# SCH_WiFiBTBitbanging_2025-02-11.net
KiCad netlist of a schematic drawn in EasyEDA
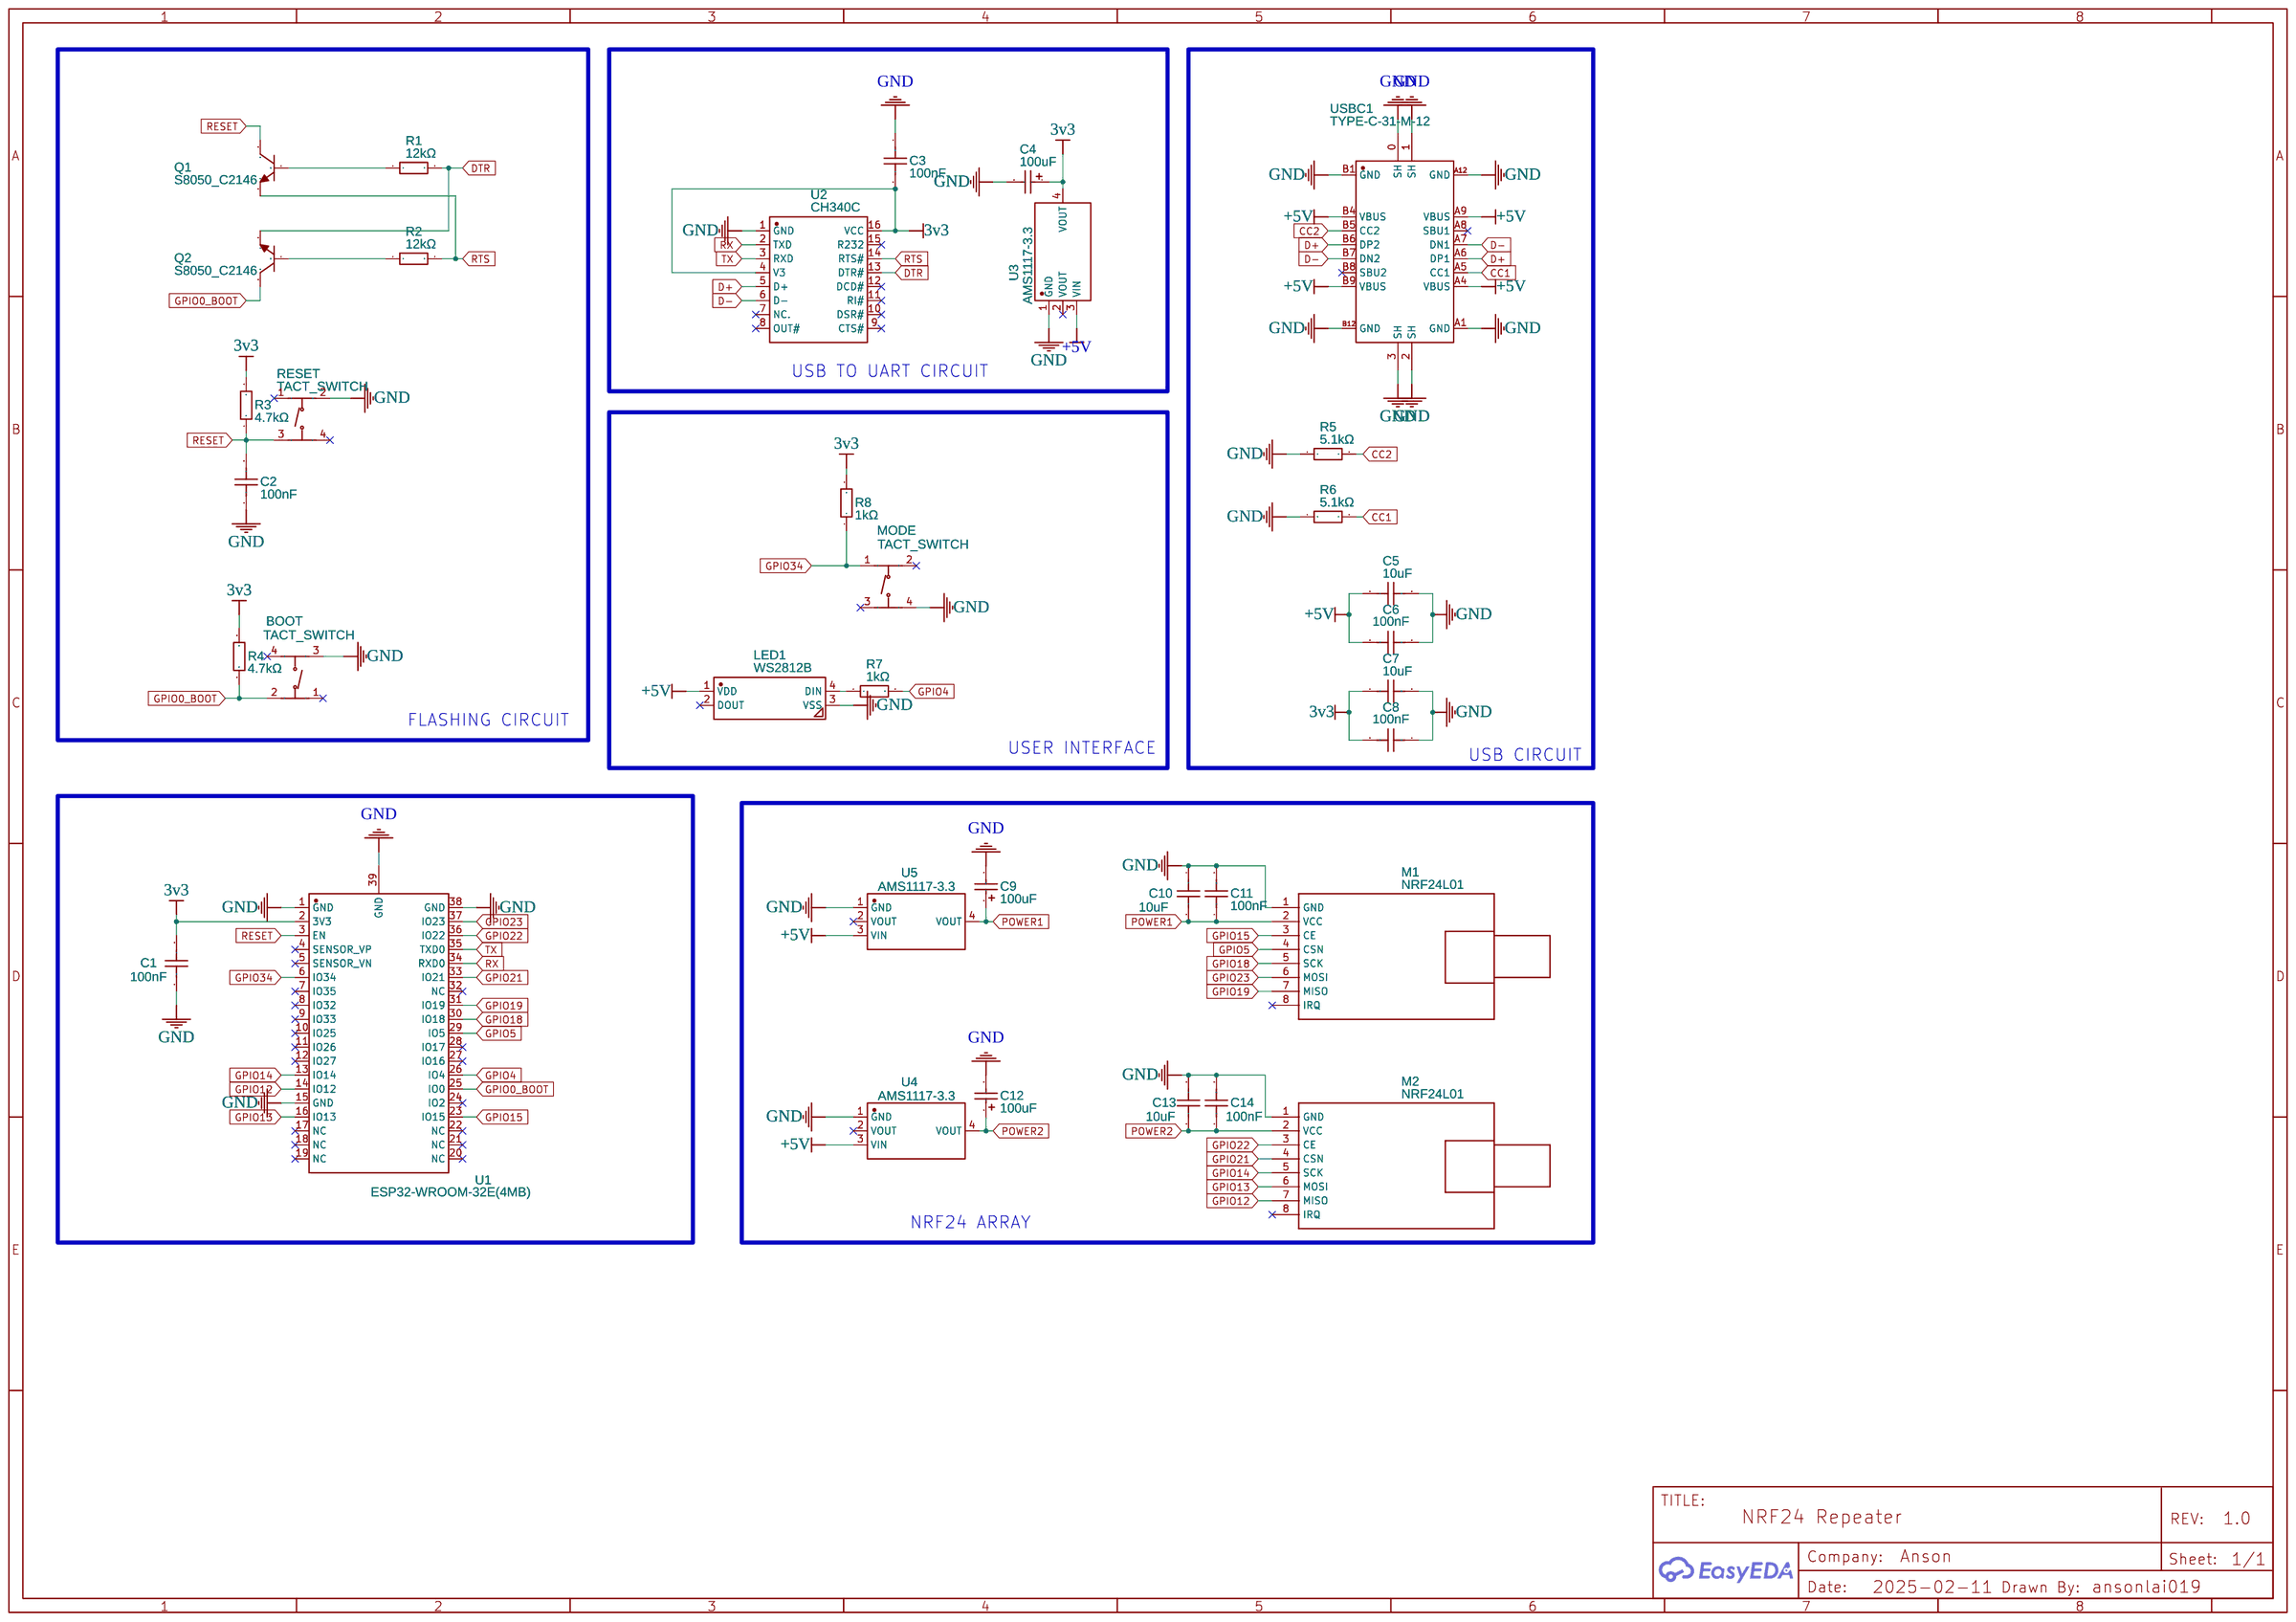
[diagram p0: schematic sheet]

(export (version "E")
  (design (tool "Eeschema 10.0.6"))
  (components
    (comp (ref "BOOT")
      (value "TACT_SWITCH")
      (fields
        (field (name "Manufacturer Part") "TS-1187A-B-A-B")
        (field (name "Manufacturer") "XKB Connectivity(中国星坤)")
      )
      (libsource (lib "") (part "TS-1187A-B-A-B"))
    )
    (comp (ref "C1")
      (value "100nF")
      (fields
        (field (name "Manufacturer Part") "CC0805KRX7R9BB104")
        (field (name "Manufacturer") "YAGEO(国巨)")
      )
      (libsource (lib "") (part "CC0805KRX7R9BB104"))
    )
    (comp (ref "C2")
      (value "100nF")
      (fields
        (field (name "Manufacturer Part") "CC0805KRX7R9BB104")
        (field (name "Manufacturer") "YAGEO(国巨)")
      )
      (libsource (lib "") (part "CC0805KRX7R9BB104"))
    )
    (comp (ref "C3")
      (value "100nF")
      (fields
        (field (name "Manufacturer Part") "CC0805KRX7R9BB104")
        (field (name "Manufacturer") "YAGEO(国巨)")
      )
      (libsource (lib "") (part "CC0805KRX7R9BB104_2"))
    )
    (comp (ref "C4")
      (value "100uF")
      (fields (field (name "Manufacturer Part") "TAJB107K006RNJ") (field (name "Manufacturer") "Kyocera AVX"))
      (libsource (lib "") (part "TAJB107K006RNJ_1"))
    )
    (comp (ref "C5")
      (value "10uF")
      (fields
        (field (name "Manufacturer Part") "CL21A106KAYNNNE")
        (field (name "Manufacturer") "SAMSUNG(三星)")
      )
      (libsource (lib "") (part "CL21A106KAYNNNE"))
    )
    (comp (ref "C6")
      (value "100nF")
      (fields
        (field (name "Manufacturer Part") "CC0805KRX7R9BB104")
        (field (name "Manufacturer") "YAGEO(国巨)")
      )
      (libsource (lib "") (part "CC0805KRX7R9BB104_1"))
    )
    (comp (ref "C7")
      (value "10uF")
      (fields
        (field (name "Manufacturer Part") "CL21A106KAYNNNE")
        (field (name "Manufacturer") "SAMSUNG(三星)")
      )
      (libsource (lib "") (part "CL21A106KAYNNNE"))
    )
    (comp (ref "C8")
      (value "100nF")
      (fields
        (field (name "Manufacturer Part") "CC0805KRX7R9BB104")
        (field (name "Manufacturer") "YAGEO(国巨)")
      )
      (libsource (lib "") (part "CC0805KRX7R9BB104_1"))
    )
    (comp (ref "C9")
      (value "100uF")
      (fields (field (name "Manufacturer Part") "TAJB107K006RNJ") (field (name "Manufacturer") "Kyocera AVX"))
      (libsource (lib "") (part "TAJB107K006RNJ"))
    )
    (comp (ref "C10")
      (value "10uF")
      (fields
        (field (name "Manufacturer Part") "CL21A106KAYNNNE")
        (field (name "Manufacturer") "SAMSUNG(三星)")
      )
      (libsource (lib "") (part "CL21A106KAYNNNE_1"))
    )
    (comp (ref "C11")
      (value "100nF")
      (fields
        (field (name "Manufacturer Part") "CC0805KRX7R9BB104")
        (field (name "Manufacturer") "YAGEO(国巨)")
      )
      (libsource (lib "") (part "CC0805KRX7R9BB104"))
    )
    (comp (ref "C12")
      (value "100uF")
      (fields (field (name "Manufacturer Part") "TAJB107K006RNJ") (field (name "Manufacturer") "Kyocera AVX"))
      (libsource (lib "") (part "TAJB107K006RNJ"))
    )
    (comp (ref "C13")
      (value "10uF")
      (fields
        (field (name "Manufacturer Part") "CL21A106KAYNNNE")
        (field (name "Manufacturer") "SAMSUNG(三星)")
      )
      (libsource (lib "") (part "CL21A106KAYNNNE_1"))
    )
    (comp (ref "C14")
      (value "100nF")
      (fields
        (field (name "Manufacturer Part") "CC0805KRX7R9BB104")
        (field (name "Manufacturer") "YAGEO(国巨)")
      )
      (libsource (lib "") (part "CC0805KRX7R9BB104"))
    )
    (comp (ref "LED1")
      (value "WS2812B")
      (fields (field (name "Manufacturer Part") "WS2812B-B/T") (field (name "Manufacturer") "worldsemi"))
      (libsource (lib "") (part "WS2812B-B/W"))
    )
    (comp (ref "M1") (value "NRF24L01") (libsource (lib "") (part "WIRELESS-NRF24L01-PA-EXT")))
    (comp (ref "M2") (value "NRF24L01") (libsource (lib "") (part "WIRELESS-NRF24L01-PA-EXT")))
    (comp (ref "MODE")
      (value "TACT_SWITCH")
      (fields
        (field (name "Manufacturer Part") "TS-1187A-B-A-B")
        (field (name "Manufacturer") "XKB Connectivity(中国星坤)")
      )
      (libsource (lib "") (part "TS-1187A-B-A-B_2"))
    )
    (comp (ref "Q1")
      (value "S8050_C2146")
      (fields
        (field (name "Manufacturer Part") "S8050 J3Y(RANGE:200-350)")
        (field (name "Manufacturer") "CJ(江苏长电/长晶)")
      )
      (libsource (lib "") (part "S8050_C2146_1"))
    )
    (comp (ref "Q2")
      (value "S8050_C2146")
      (fields
        (field (name "Manufacturer Part") "S8050 J3Y(RANGE:200-350)")
        (field (name "Manufacturer") "CJ(江苏长电/长晶)")
      )
      (libsource (lib "") (part "S8050_C2146"))
    )
    (comp (ref "R1")
      (value "12kΩ")
      (fields
        (field (name "Manufacturer Part") "0805W8F1202T5E")
        (field (name "Manufacturer") "UNI-ROYAL(厚声)")
      )
      (libsource (lib "") (part "0805W8F1202T5E"))
    )
    (comp (ref "R2")
      (value "12kΩ")
      (fields
        (field (name "Manufacturer Part") "0805W8F1202T5E")
        (field (name "Manufacturer") "UNI-ROYAL(厚声)")
      )
      (libsource (lib "") (part "0805W8F1202T5E"))
    )
    (comp (ref "R3")
      (value "4.7kΩ")
      (fields
        (field (name "Manufacturer Part") "0805W8F4701T5E")
        (field (name "Manufacturer") "UNI-ROYAL(厚声)")
      )
      (libsource (lib "") (part "0805W8F4701T5E"))
    )
    (comp (ref "R4")
      (value "4.7kΩ")
      (fields
        (field (name "Manufacturer Part") "0805W8F4701T5E")
        (field (name "Manufacturer") "UNI-ROYAL(厚声)")
      )
      (libsource (lib "") (part "0805W8F4701T5E"))
    )
    (comp (ref "R5")
      (value "5.1kΩ")
      (fields
        (field (name "Manufacturer Part") "0805W8F5101T5E")
        (field (name "Manufacturer") "UNI-ROYAL(厚声)")
      )
      (libsource (lib "") (part "0805W8F5101T5E"))
    )
    (comp (ref "R6")
      (value "5.1kΩ")
      (fields
        (field (name "Manufacturer Part") "0805W8F5101T5E")
        (field (name "Manufacturer") "UNI-ROYAL(厚声)")
      )
      (libsource (lib "") (part "0805W8F5101T5E"))
    )
    (comp (ref "R7")
      (value "1kΩ")
      (fields
        (field (name "Manufacturer Part") "0805W8F1001T5E")
        (field (name "Manufacturer") "UNI-ROYAL(厚声)")
      )
      (libsource (lib "") (part "0805W8F1001T5E"))
    )
    (comp (ref "R8")
      (value "1kΩ")
      (fields
        (field (name "Manufacturer Part") "0805W8F1001T5E")
        (field (name "Manufacturer") "UNI-ROYAL(厚声)")
      )
      (libsource (lib "") (part "0805W8F1001T5E_1"))
    )
    (comp (ref "RESET")
      (value "TACT_SWITCH")
      (fields
        (field (name "Manufacturer Part") "TS-1187A-B-A-B")
        (field (name "Manufacturer") "XKB Connectivity(中国星坤)")
      )
      (libsource (lib "") (part "TS-1187A-B-A-B_1"))
    )
    (comp (ref "U1")
      (value "ESP32-WROOM-32E(4MB)")
      (fields
        (field (name "Manufacturer Part") "ESP32-WROOM-32E-N4")
        (field (name "Manufacturer") "ESPRESSIF(乐鑫)")
      )
      (libsource (lib "") (part "ESP32-WROOM-32E(4MB)"))
    )
    (comp (ref "U2")
      (value "CH340C")
      (fields (field (name "Manufacturer") "WCH(南京沁恒)"))
      (libsource (lib "") (part "CH340C"))
    )
    (comp (ref "U3")
      (value "AMS1117-3.3")
      (fields (field (name "Manufacturer") "AMS"))
      (libsource (lib "") (part "AMS1117-3.3"))
    )
    (comp (ref "U4")
      (value "AMS1117-3.3")
      (fields (field (name "Manufacturer") "AMS"))
      (libsource (lib "") (part "AMS1117-3.3_1"))
    )
    (comp (ref "U5")
      (value "AMS1117-3.3")
      (fields (field (name "Manufacturer") "AMS"))
      (libsource (lib "") (part "AMS1117-3.3_1"))
    )
    (comp (ref "USBC1")
      (value "TYPE-C-31-M-12")
      (fields (field (name "Manufacturer") "韩国韩荣"))
      (libsource (lib "") (part "TYPE-C-31-M-12"))
    )
  )
  (nets
    (net (code "1") (name "+5V") (class "Default")
      (node (ref "C5") (pin "1") (pinfunction "1_1") (pintype "unspecified"))
      (node (ref "C6") (pin "2") (pinfunction "2_2") (pintype "unspecified"))
      (node (ref "LED1") (pin "1") (pinfunction "VDD_1") (pintype "unspecified"))
      (node (ref "U3") (pin "3") (pinfunction "VIN_3") (pintype "unspecified"))
      (node (ref "U4") (pin "3") (pinfunction "VIN_3") (pintype "unspecified"))
      (node (ref "U5") (pin "3") (pinfunction "VIN_3") (pintype "unspecified"))
      (node (ref "USBC1") (pin "A4") (pinfunction "VBUS_A4") (pintype "unspecified"))
      (node (ref "USBC1") (pin "A9") (pinfunction "VBUS_A9") (pintype "unspecified"))
      (node (ref "USBC1") (pin "B4") (pinfunction "VBUS_B4") (pintype "unspecified"))
      (node (ref "USBC1") (pin "B9") (pinfunction "VBUS_B9") (pintype "unspecified"))
    )
    (net (code "2") (name "3v3") (class "Default")
      (node (ref "C1") (pin "2") (pinfunction "2_2") (pintype "unspecified"))
      (node (ref "C3") (pin "2") (pinfunction "2_2") (pintype "unspecified"))
      (node (ref "C4") (pin "1") (pinfunction "1_1") (pintype "input"))
      (node (ref "C7") (pin "1") (pinfunction "1_1") (pintype "unspecified"))
      (node (ref "C8") (pin "2") (pinfunction "2_2") (pintype "unspecified"))
      (node (ref "R3") (pin "2") (pinfunction "2_2") (pintype "input"))
      (node (ref "R4") (pin "2") (pinfunction "2_2") (pintype "input"))
      (node (ref "R8") (pin "2") (pinfunction "2_2") (pintype "input"))
      (node (ref "U1") (pin "2") (pinfunction "3V3_2") (pintype "unspecified"))
      (node (ref "U2") (pin "16") (pinfunction "VCC_16") (pintype "unspecified"))
      (node (ref "U2") (pin "4") (pinfunction "V3_4") (pintype "unspecified"))
      (node (ref "U3") (pin "4") (pinfunction "VOUT_4") (pintype "unspecified"))
    )
    (net (code "3") (name "CC1") (class "Default")
      (node (ref "R6") (pin "2") (pinfunction "2_2") (pintype "input"))
      (node (ref "USBC1") (pin "A5") (pinfunction "CC1_A5") (pintype "unspecified"))
    )
    (net (code "4") (name "CC2") (class "Default")
      (node (ref "R5") (pin "2") (pinfunction "2_2") (pintype "input"))
      (node (ref "USBC1") (pin "B5") (pinfunction "CC2_B5") (pintype "unspecified"))
    )
    (net (code "5") (name "D+") (class "Default")
      (node (ref "U2") (pin "5") (pinfunction "D+_5") (pintype "unspecified"))
      (node (ref "USBC1") (pin "A6") (pinfunction "DP1_A6") (pintype "unspecified"))
      (node (ref "USBC1") (pin "B6") (pinfunction "DP2_B6") (pintype "unspecified"))
    )
    (net (code "6") (name "D-") (class "Default")
      (node (ref "U2") (pin "6") (pinfunction "D-_6") (pintype "unspecified"))
      (node (ref "USBC1") (pin "A7") (pinfunction "DN1_A7") (pintype "unspecified"))
      (node (ref "USBC1") (pin "B7") (pinfunction "DN2_B7") (pintype "unspecified"))
    )
    (net (code "7") (name "DTR") (class "Default")
      (node (ref "Q2") (pin "2") (pinfunction "E_2") (pintype "unspecified"))
      (node (ref "R1") (pin "2") (pinfunction "2_2") (pintype "input"))
      (node (ref "U2") (pin "13") (pinfunction "DTR#_13") (pintype "unspecified"))
    )
    (net (code "8") (name "GND") (class "Default")
      (node (ref "BOOT") (pin "3") (pinfunction "C_3") (pintype "unspecified"))
      (node (ref "C1") (pin "1") (pinfunction "1_1") (pintype "unspecified"))
      (node (ref "C10") (pin "1") (pinfunction "1_1") (pintype "unspecified"))
      (node (ref "C11") (pin "2") (pinfunction "2_2") (pintype "unspecified"))
      (node (ref "C12") (pin "2") (pinfunction "2_2") (pintype "input"))
      (node (ref "C13") (pin "1") (pinfunction "1_1") (pintype "unspecified"))
      (node (ref "C14") (pin "2") (pinfunction "2_2") (pintype "unspecified"))
      (node (ref "C2") (pin "1") (pinfunction "1_1") (pintype "unspecified"))
      (node (ref "C3") (pin "1") (pinfunction "1_1") (pintype "unspecified"))
      (node (ref "C4") (pin "2") (pinfunction "2_2") (pintype "input"))
      (node (ref "C5") (pin "2") (pinfunction "2_2") (pintype "unspecified"))
      (node (ref "C6") (pin "1") (pinfunction "1_1") (pintype "unspecified"))
      (node (ref "C7") (pin "2") (pinfunction "2_2") (pintype "unspecified"))
      (node (ref "C8") (pin "1") (pinfunction "1_1") (pintype "unspecified"))
      (node (ref "C9") (pin "2") (pinfunction "2_2") (pintype "input"))
      (node (ref "LED1") (pin "3") (pinfunction "VSS_3") (pintype "unspecified"))
      (node (ref "M1") (pin "1") (pinfunction "GND_1") (pintype "bidirectional"))
      (node (ref "M2") (pin "1") (pinfunction "GND_1") (pintype "bidirectional"))
      (node (ref "MODE") (pin "4") (pinfunction "D_4") (pintype "unspecified"))
      (node (ref "R5") (pin "1") (pinfunction "1_1") (pintype "input"))
      (node (ref "R6") (pin "1") (pinfunction "1_1") (pintype "input"))
      (node (ref "RESET") (pin "2") (pinfunction "B_2") (pintype "unspecified"))
      (node (ref "U1") (pin "1") (pinfunction "GND_1") (pintype "unspecified"))
      (node (ref "U1") (pin "15") (pinfunction "GND_15") (pintype "unspecified"))
      (node (ref "U1") (pin "38") (pinfunction "GND_38") (pintype "unspecified"))
      (node (ref "U1") (pin "39") (pinfunction "GND_39") (pintype "unspecified"))
      (node (ref "U2") (pin "1") (pinfunction "GND_1") (pintype "unspecified"))
      (node (ref "U3") (pin "1") (pinfunction "GND_1") (pintype "unspecified"))
      (node (ref "U4") (pin "1") (pinfunction "GND_1") (pintype "unspecified"))
      (node (ref "U5") (pin "1") (pinfunction "GND_1") (pintype "unspecified"))
      (node (ref "USBC1") (pin "0") (pinfunction "SH_0") (pintype "unspecified"))
      (node (ref "USBC1") (pin "1") (pinfunction "SH_1") (pintype "unspecified"))
      (node (ref "USBC1") (pin "2") (pinfunction "SH_2") (pintype "unspecified"))
      (node (ref "USBC1") (pin "3") (pinfunction "SH_3") (pintype "unspecified"))
      (node (ref "USBC1") (pin "A1") (pinfunction "GND_A1") (pintype "unspecified"))
      (node (ref "USBC1") (pin "A12") (pinfunction "GND_A12") (pintype "unspecified"))
      (node (ref "USBC1") (pin "B1") (pinfunction "GND_B1") (pintype "unspecified"))
      (node (ref "USBC1") (pin "B12") (pinfunction "GND_B12") (pintype "unspecified"))
    )
    (net (code "9") (name "GPIO0_BOOT") (class "Default")
      (node (ref "BOOT") (pin "2") (pinfunction "B_2") (pintype "unspecified"))
      (node (ref "Q2") (pin "3") (pinfunction "C_3") (pintype "unspecified"))
      (node (ref "R4") (pin "1") (pinfunction "1_1") (pintype "input"))
      (node (ref "U1") (pin "25") (pinfunction "IO0_25") (pintype "unspecified"))
    )
    (net (code "10") (name "GPIO4") (class "Default")
      (node (ref "R7") (pin "2") (pinfunction "2_2") (pintype "input"))
      (node (ref "U1") (pin "26") (pinfunction "IO4_26") (pintype "unspecified"))
    )
    (net (code "11") (name "GPIO5") (class "Default")
      (node (ref "M1") (pin "4") (pinfunction "CSN_4") (pintype "bidirectional"))
      (node (ref "U1") (pin "29") (pinfunction "IO5_29") (pintype "unspecified"))
    )
    (net (code "12") (name "GPIO12") (class "Default")
      (node (ref "M2") (pin "7") (pinfunction "MISO_7") (pintype "bidirectional"))
      (node (ref "U1") (pin "14") (pinfunction "IO12_14") (pintype "unspecified"))
    )
    (net (code "13") (name "GPIO13") (class "Default")
      (node (ref "M2") (pin "6") (pinfunction "MOSI_6") (pintype "bidirectional"))
      (node (ref "U1") (pin "16") (pinfunction "IO13_16") (pintype "unspecified"))
    )
    (net (code "14") (name "GPIO14") (class "Default")
      (node (ref "M2") (pin "5") (pinfunction "SCK_5") (pintype "bidirectional"))
      (node (ref "U1") (pin "13") (pinfunction "IO14_13") (pintype "unspecified"))
    )
    (net (code "15") (name "GPIO15") (class "Default")
      (node (ref "M1") (pin "3") (pinfunction "CE_3") (pintype "bidirectional"))
      (node (ref "U1") (pin "23") (pinfunction "IO15_23") (pintype "unspecified"))
    )
    (net (code "16") (name "GPIO18") (class "Default")
      (node (ref "M1") (pin "5") (pinfunction "SCK_5") (pintype "bidirectional"))
      (node (ref "U1") (pin "30") (pinfunction "IO18_30") (pintype "unspecified"))
    )
    (net (code "17") (name "GPIO19") (class "Default")
      (node (ref "M1") (pin "7") (pinfunction "MISO_7") (pintype "bidirectional"))
      (node (ref "U1") (pin "31") (pinfunction "IO19_31") (pintype "unspecified"))
    )
    (net (code "18") (name "GPIO21") (class "Default")
      (node (ref "M2") (pin "4") (pinfunction "CSN_4") (pintype "bidirectional"))
      (node (ref "U1") (pin "33") (pinfunction "IO21_33") (pintype "unspecified"))
    )
    (net (code "19") (name "GPIO22") (class "Default")
      (node (ref "M2") (pin "3") (pinfunction "CE_3") (pintype "bidirectional"))
      (node (ref "U1") (pin "36") (pinfunction "IO22_36") (pintype "unspecified"))
    )
    (net (code "20") (name "GPIO23") (class "Default")
      (node (ref "M1") (pin "6") (pinfunction "MOSI_6") (pintype "bidirectional"))
      (node (ref "U1") (pin "37") (pinfunction "IO23_37") (pintype "unspecified"))
    )
    (net (code "21") (name "GPIO34") (class "Default")
      (node (ref "MODE") (pin "1") (pinfunction "A_1") (pintype "unspecified"))
      (node (ref "R8") (pin "1") (pinfunction "1_1") (pintype "input"))
      (node (ref "U1") (pin "6") (pinfunction "IO34_6") (pintype "unspecified"))
    )
    (net (code "22") (name "Net-(LED1-DIN)") (class "Default")
      (node (ref "LED1") (pin "4") (pinfunction "DIN_4") (pintype "unspecified"))
      (node (ref "R7") (pin "1") (pinfunction "1_1") (pintype "input"))
    )
    (net (code "23") (name "Net-(Q1-B)") (class "Default")
      (node (ref "Q1") (pin "1") (pinfunction "B_1") (pintype "unspecified"))
      (node (ref "R1") (pin "1") (pinfunction "1_1") (pintype "input"))
    )
    (net (code "24") (name "Net-(Q2-B)") (class "Default")
      (node (ref "Q2") (pin "1") (pinfunction "B_1") (pintype "unspecified"))
      (node (ref "R2") (pin "1") (pinfunction "1_1") (pintype "input"))
    )
    (net (code "25") (name "POWER1") (class "Default")
      (node (ref "C10") (pin "2") (pinfunction "2_2") (pintype "unspecified"))
      (node (ref "C11") (pin "1") (pinfunction "1_1") (pintype "unspecified"))
      (node (ref "C9") (pin "1") (pinfunction "1_1") (pintype "input"))
      (node (ref "M1") (pin "2") (pinfunction "VCC_2") (pintype "bidirectional"))
      (node (ref "U5") (pin "4") (pinfunction "VOUT_4") (pintype "unspecified"))
    )
    (net (code "26") (name "POWER2") (class "Default")
      (node (ref "C12") (pin "1") (pinfunction "1_1") (pintype "input"))
      (node (ref "C13") (pin "2") (pinfunction "2_2") (pintype "unspecified"))
      (node (ref "C14") (pin "1") (pinfunction "1_1") (pintype "unspecified"))
      (node (ref "M2") (pin "2") (pinfunction "VCC_2") (pintype "bidirectional"))
      (node (ref "U4") (pin "4") (pinfunction "VOUT_4") (pintype "unspecified"))
    )
    (net (code "27") (name "RESET") (class "Default")
      (node (ref "C2") (pin "2") (pinfunction "2_2") (pintype "unspecified"))
      (node (ref "Q1") (pin "3") (pinfunction "C_3") (pintype "unspecified"))
      (node (ref "R3") (pin "1") (pinfunction "1_1") (pintype "input"))
      (node (ref "RESET") (pin "3") (pinfunction "C_3") (pintype "unspecified"))
      (node (ref "U1") (pin "3") (pinfunction "EN_3") (pintype "unspecified"))
    )
    (net (code "28") (name "RTS") (class "Default")
      (node (ref "Q1") (pin "2") (pinfunction "E_2") (pintype "unspecified"))
      (node (ref "R2") (pin "2") (pinfunction "2_2") (pintype "input"))
      (node (ref "U2") (pin "14") (pinfunction "RTS#_14") (pintype "unspecified"))
    )
    (net (code "29") (name "RX") (class "Default")
      (node (ref "U1") (pin "34") (pinfunction "RXD0_34") (pintype "unspecified"))
      (node (ref "U2") (pin "2") (pinfunction "TXD_2") (pintype "unspecified"))
    )
    (net (code "30") (name "TX") (class "Default")
      (node (ref "U1") (pin "35") (pinfunction "TXD0_35") (pintype "unspecified"))
      (node (ref "U2") (pin "3") (pinfunction "RXD_3") (pintype "unspecified"))
    )
    (net (code "31") (name "unconnected-(BOOT-A-Pad1)") (class "Default")
      (node (ref "BOOT") (pin "1") (pinfunction "A_1") (pintype "unspecified+no_connect"))
    )
    (net (code "32") (name "unconnected-(BOOT-D-Pad4)") (class "Default")
      (node (ref "BOOT") (pin "4") (pinfunction "D_4") (pintype "unspecified+no_connect"))
    )
    (net (code "33") (name "unconnected-(LED1-DOUT-Pad2)") (class "Default")
      (node (ref "LED1") (pin "2") (pinfunction "DOUT_2") (pintype "unspecified+no_connect"))
    )
    (net (code "34") (name "unconnected-(M1-IRQ-Pad8)") (class "Default")
      (node (ref "M1") (pin "8") (pinfunction "IRQ_8") (pintype "bidirectional+no_connect"))
    )
    (net (code "35") (name "unconnected-(M2-IRQ-Pad8)") (class "Default")
      (node (ref "M2") (pin "8") (pinfunction "IRQ_8") (pintype "bidirectional+no_connect"))
    )
    (net (code "36") (name "unconnected-(MODE-B-Pad2)") (class "Default")
      (node (ref "MODE") (pin "2") (pinfunction "B_2") (pintype "unspecified+no_connect"))
    )
    (net (code "37") (name "unconnected-(MODE-C-Pad3)") (class "Default")
      (node (ref "MODE") (pin "3") (pinfunction "C_3") (pintype "unspecified+no_connect"))
    )
    (net (code "38") (name "unconnected-(RESET-A-Pad1)") (class "Default")
      (node (ref "RESET") (pin "1") (pinfunction "A_1") (pintype "unspecified+no_connect"))
    )
    (net (code "39") (name "unconnected-(RESET-D-Pad4)") (class "Default")
      (node (ref "RESET") (pin "4") (pinfunction "D_4") (pintype "unspecified+no_connect"))
    )
    (net (code "40") (name "unconnected-(U1-IO2-Pad24)") (class "Default")
      (node (ref "U1") (pin "24") (pinfunction "IO2_24") (pintype "unspecified+no_connect"))
    )
    (net (code "41") (name "unconnected-(U1-IO16-Pad27)") (class "Default")
      (node (ref "U1") (pin "27") (pinfunction "IO16_27") (pintype "unspecified+no_connect"))
    )
    (net (code "42") (name "unconnected-(U1-IO17-Pad28)") (class "Default")
      (node (ref "U1") (pin "28") (pinfunction "IO17_28") (pintype "unspecified+no_connect"))
    )
    (net (code "43") (name "unconnected-(U1-IO25-Pad10)") (class "Default")
      (node (ref "U1") (pin "10") (pinfunction "IO25_10") (pintype "unspecified+no_connect"))
    )
    (net (code "44") (name "unconnected-(U1-IO26-Pad11)") (class "Default")
      (node (ref "U1") (pin "11") (pinfunction "IO26_11") (pintype "unspecified+no_connect"))
    )
    (net (code "45") (name "unconnected-(U1-IO27-Pad12)") (class "Default")
      (node (ref "U1") (pin "12") (pinfunction "IO27_12") (pintype "unspecified+no_connect"))
    )
    (net (code "46") (name "unconnected-(U1-IO32-Pad8)") (class "Default")
      (node (ref "U1") (pin "8") (pinfunction "IO32_8") (pintype "unspecified+no_connect"))
    )
    (net (code "47") (name "unconnected-(U1-IO33-Pad9)") (class "Default")
      (node (ref "U1") (pin "9") (pinfunction "IO33_9") (pintype "unspecified+no_connect"))
    )
    (net (code "48") (name "unconnected-(U1-IO35-Pad7)") (class "Default")
      (node (ref "U1") (pin "7") (pinfunction "IO35_7") (pintype "unspecified+no_connect"))
    )
    (net (code "49") (name "unconnected-(U1-NC-Pad17)") (class "Default")
      (node (ref "U1") (pin "17") (pinfunction "NC_17") (pintype "unspecified+no_connect"))
    )
    (net (code "50") (name "unconnected-(U1-NC-Pad18)") (class "Default")
      (node (ref "U1") (pin "18") (pinfunction "NC_18") (pintype "unspecified+no_connect"))
    )
    (net (code "51") (name "unconnected-(U1-NC-Pad19)") (class "Default")
      (node (ref "U1") (pin "19") (pinfunction "NC_19") (pintype "unspecified+no_connect"))
    )
    (net (code "52") (name "unconnected-(U1-NC-Pad20)") (class "Default")
      (node (ref "U1") (pin "20") (pinfunction "NC_20") (pintype "unspecified+no_connect"))
    )
    (net (code "53") (name "unconnected-(U1-NC-Pad21)") (class "Default")
      (node (ref "U1") (pin "21") (pinfunction "NC_21") (pintype "unspecified+no_connect"))
    )
    (net (code "54") (name "unconnected-(U1-NC-Pad22)") (class "Default")
      (node (ref "U1") (pin "22") (pinfunction "NC_22") (pintype "unspecified+no_connect"))
    )
    (net (code "55") (name "unconnected-(U1-NC-Pad32)") (class "Default")
      (node (ref "U1") (pin "32") (pinfunction "NC_32") (pintype "unspecified+no_connect"))
    )
    (net (code "56") (name "unconnected-(U1-SENSOR_VN-Pad5)") (class "Default")
      (node (ref "U1") (pin "5") (pinfunction "SENSOR_VN_5") (pintype "unspecified+no_connect"))
    )
    (net (code "57") (name "unconnected-(U1-SENSOR_VP-Pad4)") (class "Default")
      (node (ref "U1") (pin "4") (pinfunction "SENSOR_VP_4") (pintype "unspecified+no_connect"))
    )
    (net (code "58") (name "unconnected-(U2-CTS#-Pad9)") (class "Default")
      (node (ref "U2") (pin "9") (pinfunction "CTS#_9") (pintype "unspecified+no_connect"))
    )
    (net (code "59") (name "unconnected-(U2-DCD#-Pad12)") (class "Default")
      (node (ref "U2") (pin "12") (pinfunction "DCD#_12") (pintype "unspecified+no_connect"))
    )
    (net (code "60") (name "unconnected-(U2-DSR#-Pad10)") (class "Default")
      (node (ref "U2") (pin "10") (pinfunction "DSR#_10") (pintype "unspecified+no_connect"))
    )
    (net (code "61") (name "unconnected-(U2-NC.-Pad7)") (class "Default")
      (node (ref "U2") (pin "7") (pinfunction "NC._7") (pintype "unspecified+no_connect"))
    )
    (net (code "62") (name "unconnected-(U2-OUT#-Pad8)") (class "Default")
      (node (ref "U2") (pin "8") (pinfunction "OUT#_8") (pintype "unspecified+no_connect"))
    )
    (net (code "63") (name "unconnected-(U2-R232-Pad15)") (class "Default")
      (node (ref "U2") (pin "15") (pinfunction "R232_15") (pintype "unspecified+no_connect"))
    )
    (net (code "64") (name "unconnected-(U2-RI#-Pad11)") (class "Default")
      (node (ref "U2") (pin "11") (pinfunction "RI#_11") (pintype "unspecified+no_connect"))
    )
    (net (code "65") (name "unconnected-(U3-VOUT-Pad2)") (class "Default")
      (node (ref "U3") (pin "2") (pinfunction "VOUT_2") (pintype "unspecified+no_connect"))
    )
    (net (code "66") (name "unconnected-(U4-VOUT-Pad2)") (class "Default")
      (node (ref "U4") (pin "2") (pinfunction "VOUT_2") (pintype "unspecified+no_connect"))
    )
    (net (code "67") (name "unconnected-(U5-VOUT-Pad2)") (class "Default")
      (node (ref "U5") (pin "2") (pinfunction "VOUT_2") (pintype "unspecified+no_connect"))
    )
    (net (code "68") (name "unconnected-(USBC1-SBU1-PadA8)") (class "Default")
      (node (ref "USBC1") (pin "A8") (pinfunction "SBU1_A8") (pintype "unspecified+no_connect"))
    )
    (net (code "69") (name "unconnected-(USBC1-SBU2-PadB8)") (class "Default")
      (node (ref "USBC1") (pin "B8") (pinfunction "SBU2_B8") (pintype "unspecified+no_connect"))
    )
  )
)
